# Practicum_front.net
KiCad netlist of a schematic drawn in EAGLE
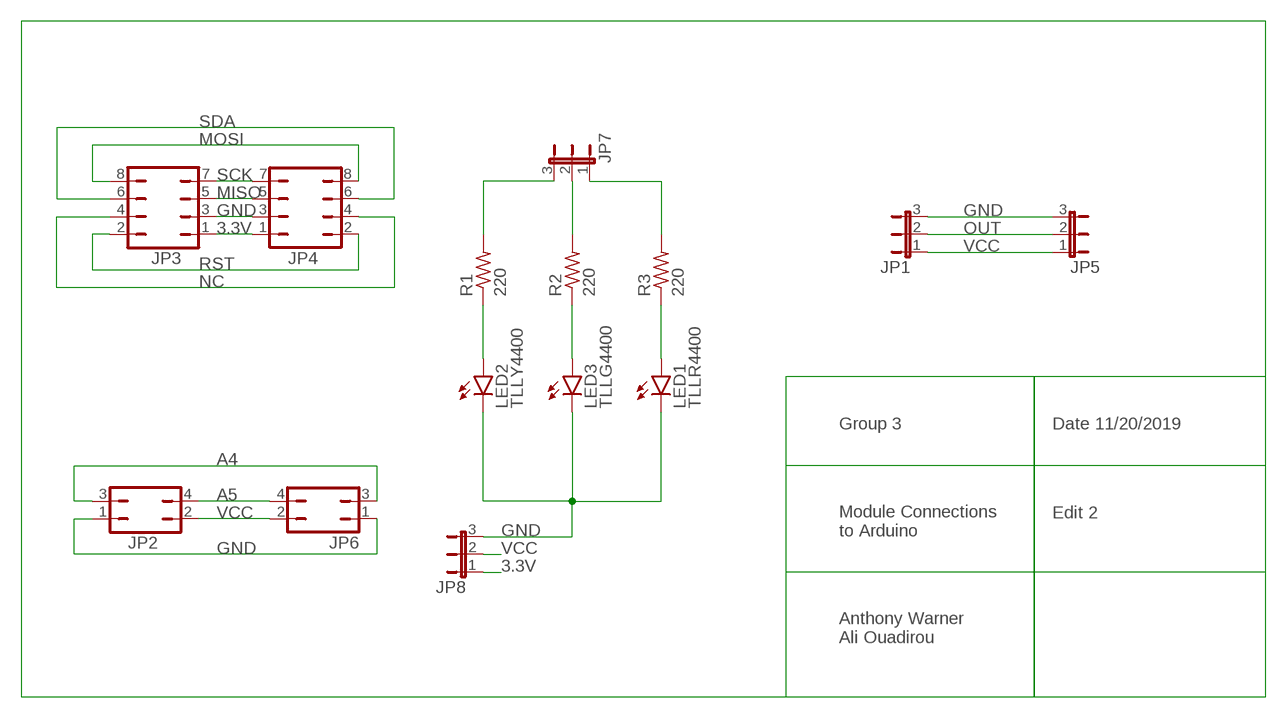
[diagram p0: schematic, sheet 1]

(export (version "E")
  (design (tool "Eeschema 10.0.6"))
  (components
    (comp (ref "JP1")
      (value "0")
      (footprint "eagle-import:JP2")
      (libsource (lib "eagle-import") (part "JP2E"))
    )
    (comp (ref "JP2")
      (value "0")
      (footprint "eagle-import:JP2Q")
      (libsource (lib "eagle-import") (part "JP2Q"))
    )
    (comp (ref "JP3")
      (value "0")
      (footprint "eagle-import:JP4Q")
      (libsource (lib "eagle-import") (part "JP4Q"))
    )
    (comp (ref "JP4")
      (value "0")
      (footprint "eagle-import:JP4Q")
      (libsource (lib "eagle-import") (part "JP4Q"))
    )
    (comp (ref "JP5")
      (value "0")
      (footprint "eagle-import:JP2")
      (libsource (lib "eagle-import") (part "JP2E"))
    )
    (comp (ref "JP6")
      (value "0")
      (footprint "eagle-import:JP2Q")
      (libsource (lib "eagle-import") (part "JP2Q"))
    )
    (comp (ref "JP7")
      (value "0")
      (footprint "eagle-import:JP2")
      (libsource (lib "eagle-import") (part "JP2E"))
    )
    (comp (ref "JP8")
      (value "0")
      (footprint "eagle-import:JP2")
      (libsource (lib "eagle-import") (part "JP2E"))
    )
    (comp (ref "LED1")
      (value "TLLR4400")
      (footprint "eagle-import:LED3MM")
      (fields (field (name "MF") "VISHAY SEMICONDUCTOR"))
      (libsource (lib "eagle-import") (part "TLLR4400"))
    )
    (comp (ref "LED2")
      (value "TLLY4400")
      (footprint "eagle-import:LED3MM")
      (fields (field (name "MF") "VISHAY SEMICONDUCTOR"))
      (libsource (lib "eagle-import") (part "TLLY4400"))
    )
    (comp (ref "LED3")
      (value "TLLG4400")
      (footprint "eagle-import:LED3MM")
      (fields (field (name "MF") "VISHAY SEMICONDUCTOR"))
      (libsource (lib "eagle-import") (part "TLLG4400"))
    )
    (comp (ref "R1")
      (value "220")
      (footprint "eagle-import:M0805")
      (libsource (lib "eagle-import") (part "R-US_M0805"))
    )
    (comp (ref "R2")
      (value "220")
      (footprint "eagle-import:M0805")
      (libsource (lib "eagle-import") (part "R-US_M0805"))
    )
    (comp (ref "R3")
      (value "220")
      (footprint "eagle-import:M0805")
      (libsource (lib "eagle-import") (part "R-US_M0805"))
    )
  )
  (nets
    (net (code "1") (name "/3.3V") (class "Default")
      (node (ref "JP3") (pin "1") (pinfunction "1_1") (pintype "passive"))
      (node (ref "JP4") (pin "1") (pinfunction "1_1") (pintype "passive"))
      (node (ref "JP8") (pin "1") (pinfunction "1_1") (pintype "passive"))
    )
    (net (code "2") (name "/A4") (class "Default")
      (node (ref "JP2") (pin "3") (pinfunction "3_3") (pintype "passive"))
      (node (ref "JP6") (pin "3") (pinfunction "3_3") (pintype "passive"))
    )
    (net (code "3") (name "/A5") (class "Default")
      (node (ref "JP2") (pin "4") (pinfunction "4_4") (pintype "passive"))
      (node (ref "JP6") (pin "4") (pinfunction "4_4") (pintype "passive"))
    )
    (net (code "4") (name "/GND") (class "Default")
      (node (ref "JP1") (pin "3") (pinfunction "3_3") (pintype "passive"))
      (node (ref "JP2") (pin "1") (pinfunction "1_1") (pintype "passive"))
      (node (ref "JP3") (pin "3") (pinfunction "3_3") (pintype "passive"))
      (node (ref "JP4") (pin "3") (pinfunction "3_3") (pintype "passive"))
      (node (ref "JP5") (pin "3") (pinfunction "3_3") (pintype "passive"))
      (node (ref "JP6") (pin "1") (pinfunction "1_1") (pintype "passive"))
      (node (ref "JP8") (pin "3") (pinfunction "3_3") (pintype "passive"))
      (node (ref "LED1") (pin "K") (pinfunction "C_K") (pintype "passive"))
      (node (ref "LED2") (pin "K") (pinfunction "C_K") (pintype "passive"))
      (node (ref "LED3") (pin "K") (pinfunction "C_K") (pintype "passive"))
    )
    (net (code "5") (name "/MISO") (class "Default")
      (node (ref "JP3") (pin "5") (pinfunction "5_5") (pintype "passive"))
      (node (ref "JP4") (pin "5") (pinfunction "5_5") (pintype "passive"))
    )
    (net (code "6") (name "/MOSI") (class "Default")
      (node (ref "JP3") (pin "8") (pinfunction "8_8") (pintype "passive"))
      (node (ref "JP4") (pin "8") (pinfunction "8_8") (pintype "passive"))
    )
    (net (code "7") (name "/NC") (class "Default")
      (node (ref "JP3") (pin "4") (pinfunction "4_4") (pintype "passive"))
      (node (ref "JP4") (pin "4") (pinfunction "4_4") (pintype "passive"))
    )
    (net (code "8") (name "/OUT") (class "Default")
      (node (ref "JP1") (pin "2") (pinfunction "2_2") (pintype "passive"))
      (node (ref "JP5") (pin "2") (pinfunction "2_2") (pintype "passive"))
    )
    (net (code "9") (name "/RST") (class "Default")
      (node (ref "JP3") (pin "2") (pinfunction "2_2") (pintype "passive"))
      (node (ref "JP4") (pin "2") (pinfunction "2_2") (pintype "passive"))
    )
    (net (code "10") (name "/SCK") (class "Default")
      (node (ref "JP3") (pin "7") (pinfunction "7_7") (pintype "passive"))
      (node (ref "JP4") (pin "7") (pinfunction "7_7") (pintype "passive"))
    )
    (net (code "11") (name "/SDA") (class "Default")
      (node (ref "JP3") (pin "6") (pinfunction "6_6") (pintype "passive"))
      (node (ref "JP4") (pin "6") (pinfunction "6_6") (pintype "passive"))
    )
    (net (code "12") (name "/VCC") (class "Default")
      (node (ref "JP1") (pin "1") (pinfunction "1_1") (pintype "passive"))
      (node (ref "JP2") (pin "2") (pinfunction "2_2") (pintype "passive"))
      (node (ref "JP5") (pin "1") (pinfunction "1_1") (pintype "passive"))
      (node (ref "JP6") (pin "2") (pinfunction "2_2") (pintype "passive"))
      (node (ref "JP8") (pin "2") (pinfunction "2_2") (pintype "passive"))
    )
    (net (code "13") (name "Net-(JP7-Pad1)") (class "Default")
      (node (ref "JP7") (pin "1") (pinfunction "1_1") (pintype "passive"))
      (node (ref "R3") (pin "2") (pinfunction "2_2") (pintype "passive"))
    )
    (net (code "14") (name "Net-(JP7-Pad2)") (class "Default")
      (node (ref "JP7") (pin "2") (pinfunction "2_2") (pintype "passive"))
      (node (ref "R2") (pin "2") (pinfunction "2_2") (pintype "passive"))
    )
    (net (code "15") (name "Net-(JP7-Pad3)") (class "Default")
      (node (ref "JP7") (pin "3") (pinfunction "3_3") (pintype "passive"))
      (node (ref "R1") (pin "2") (pinfunction "2_2") (pintype "passive"))
    )
    (net (code "16") (name "Net-(LED1-PadA)") (class "Default")
      (node (ref "LED1") (pin "A") (pinfunction "A_A") (pintype "passive"))
      (node (ref "R3") (pin "1") (pinfunction "1_1") (pintype "passive"))
    )
    (net (code "17") (name "Net-(LED2-PadA)") (class "Default")
      (node (ref "LED2") (pin "A") (pinfunction "A_A") (pintype "passive"))
      (node (ref "R1") (pin "1") (pinfunction "1_1") (pintype "passive"))
    )
    (net (code "18") (name "Net-(LED3-PadA)") (class "Default")
      (node (ref "LED3") (pin "A") (pinfunction "A_A") (pintype "passive"))
      (node (ref "R2") (pin "1") (pinfunction "1_1") (pintype "passive"))
    )
  )
)
